# BrickPi_0_5.net
KiCad netlist of a schematic drawn in EAGLE
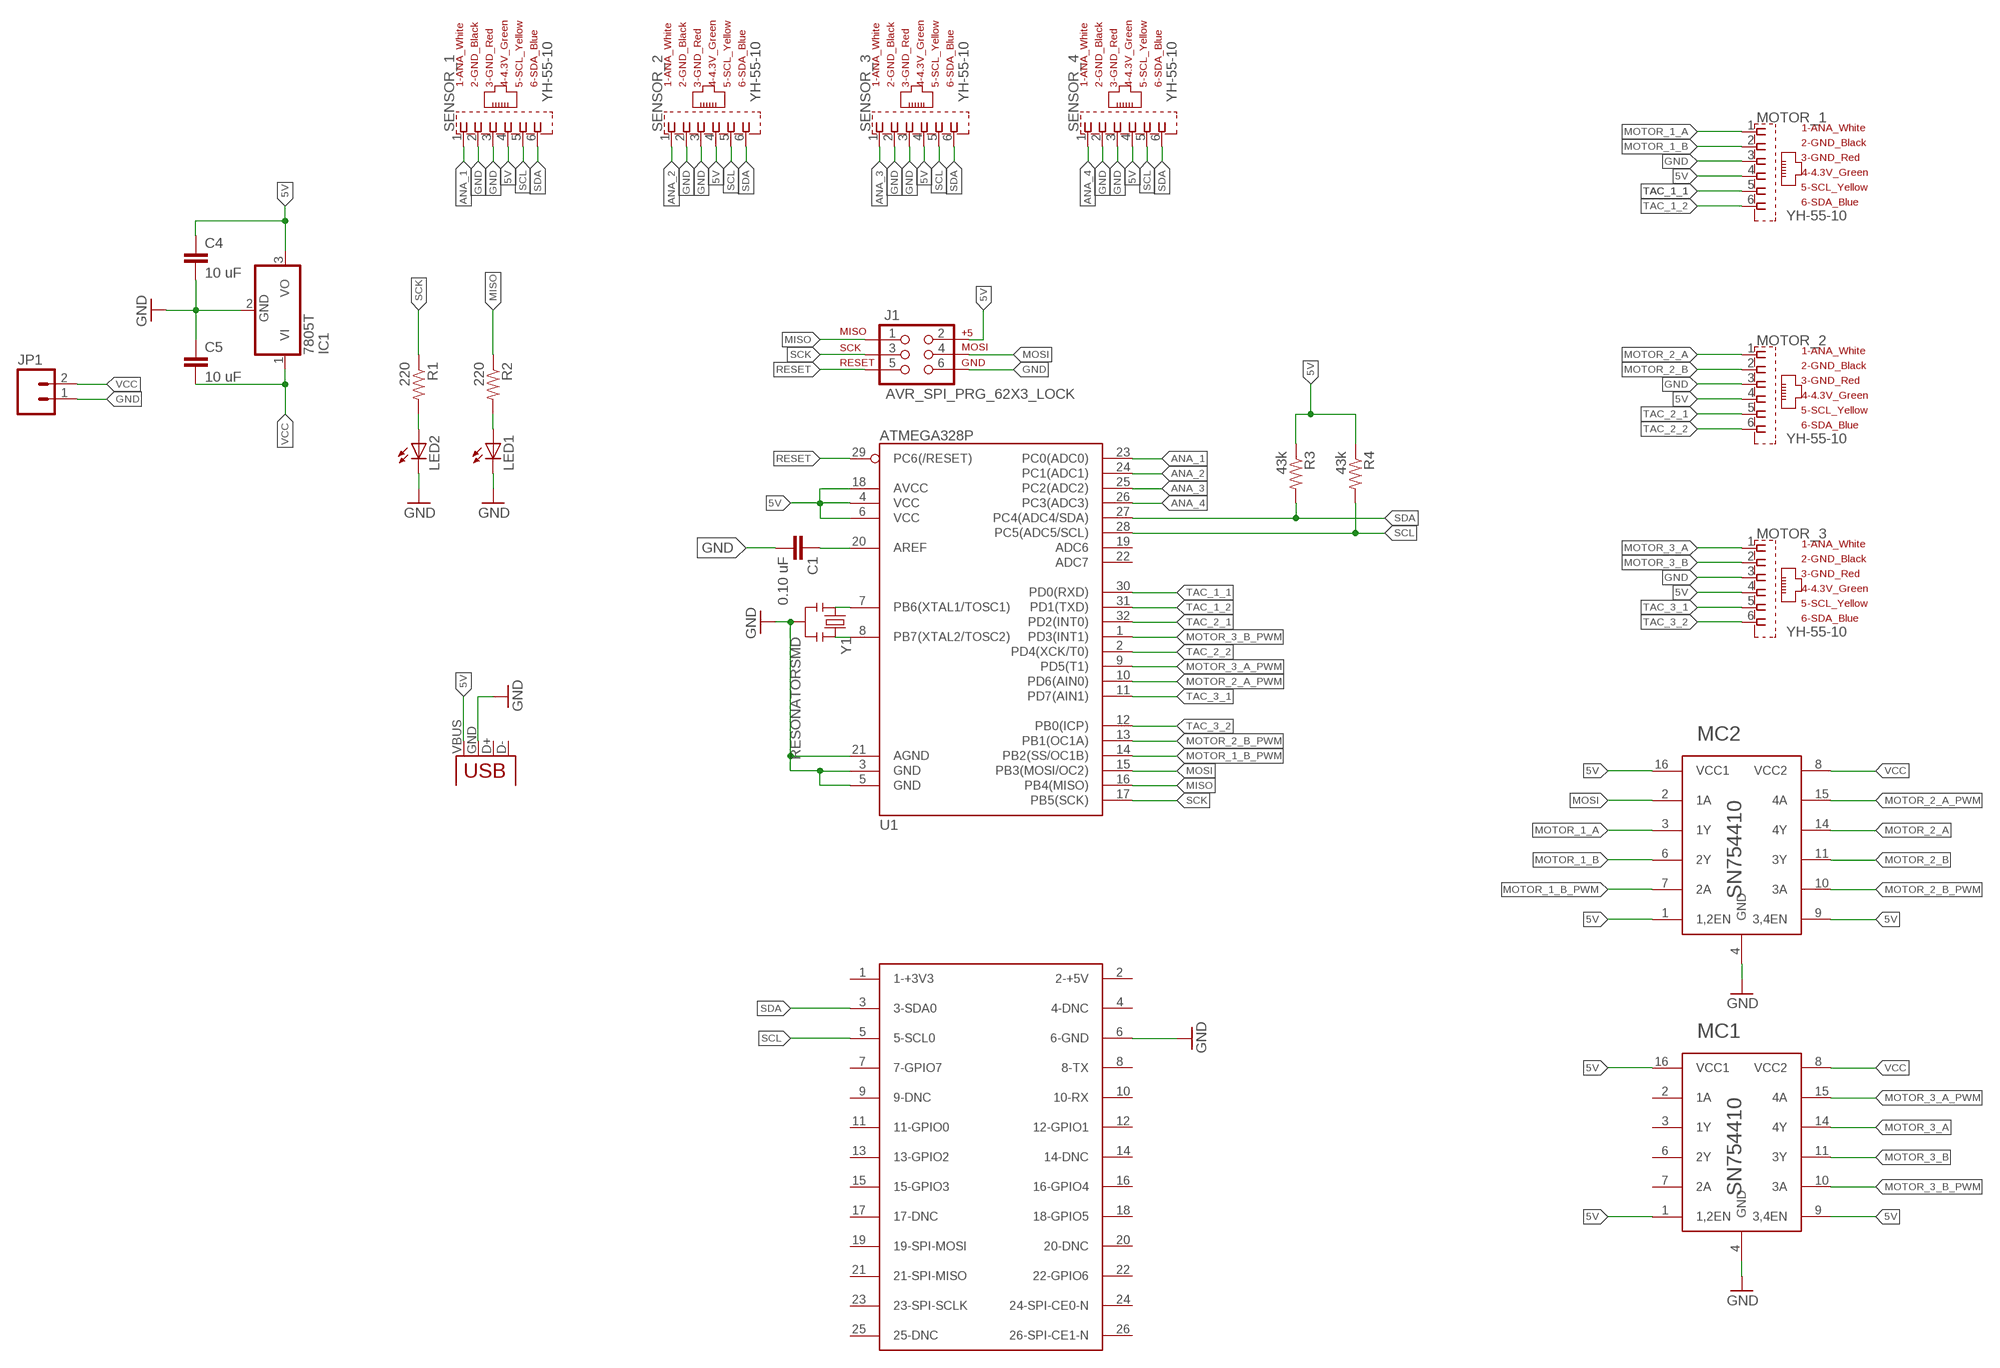
[diagram p0: schematic, sheet 1]

(export (version "E")
  (design (tool "Eeschema 10.0.6"))
  (components
    (comp (ref "C1")
      (value "0.10 uF")
      (footprint "eagle-import:0805")
      (libsource (lib "eagle-import") (part "CAP0805"))
    )
    (comp (ref "C4")
      (value "10 uF")
      (footprint "eagle-import:0805")
      (libsource (lib "eagle-import") (part "CAP0805"))
    )
    (comp (ref "C5")
      (value "10 uF")
      (footprint "eagle-import:0805")
      (libsource (lib "eagle-import") (part "CAP0805"))
    )
    (comp (ref "IC1")
      (value "7805T")
      (footprint "eagle-import:TO220H")
      (libsource (lib "eagle-import") (part "78T05"))
    )
    (comp (ref "J1")
      (value "AVR_SPI_PRG_62X3_LOCK")
      (footprint "eagle-import:2X3_LOCK")
      (libsource (lib "eagle-import") (part "AVR_SPI_PRG_62X3_LOCK"))
    )
    (comp (ref "JP1")
      (value "M02LOCK")
      (footprint "eagle-import:1X02_LOCK")
      (libsource (lib "eagle-import") (part "M02LOCK"))
    )
    (comp (ref "JP2")
      (value "USB-A-H")
      (footprint "eagle-import:USB-A-H")
      (libsource (lib "eagle-import") (part "USB-A-H"))
    )
    (comp (ref "LED1")
      (value "LED1206")
      (footprint "eagle-import:LED-1206")
      (libsource (lib "eagle-import") (part "LED1206"))
    )
    (comp (ref "LED2")
      (value "LED1206")
      (footprint "eagle-import:LED-1206")
      (libsource (lib "eagle-import") (part "LED1206"))
    )
    (comp (ref "MC1")
      (value "SN754410")
      (footprint "eagle-import:DIL16")
      (libsource (lib "eagle-import") (part "SN754410"))
    )
    (comp (ref "MC2")
      (value "SN754410")
      (footprint "eagle-import:DIL16")
      (libsource (lib "eagle-import") (part "SN754410"))
    )
    (comp (ref "MOTOR_1")
      (value "YH-55-10")
      (footprint "eagle-import:YH-55-10")
      (libsource (lib "eagle-import") (part "YH-55-10"))
    )
    (comp (ref "MOTOR_2")
      (value "YH-55-10")
      (footprint "eagle-import:YH-55-10")
      (libsource (lib "eagle-import") (part "YH-55-10"))
    )
    (comp (ref "MOTOR_3")
      (value "YH-55-10")
      (footprint "eagle-import:YH-55-10")
      (libsource (lib "eagle-import") (part "YH-55-10"))
    )
    (comp (ref "PI_OUTLINE")
      (value "RASPBERRY-PI")
      (footprint "eagle-import:RASPBERRY-PI")
      (libsource (lib "eagle-import") (part "RASPBERRY-PI"))
    )
    (comp (ref "R1")
      (value "220")
      (footprint "eagle-import:0603-RES")
      (libsource (lib "eagle-import") (part "220-5%"))
    )
    (comp (ref "R2")
      (value "220")
      (footprint "eagle-import:0603-RES")
      (libsource (lib "eagle-import") (part "220-5%"))
    )
    (comp (ref "R3")
      (value "43k")
      (footprint "eagle-import:0603-RES")
      (fields (field (name "PROD_ID") "RES-07866"))
      (libsource (lib "eagle-import") (part "220-5%"))
    )
    (comp (ref "R4")
      (value "43k")
      (footprint "eagle-import:0603-RES")
      (fields (field (name "PROD_ID") "RES-07866"))
      (libsource (lib "eagle-import") (part "220-5%"))
    )
    (comp (ref "SENSOR_1")
      (value "YH-55-10")
      (footprint "eagle-import:YH-55-10")
      (libsource (lib "eagle-import") (part "YH-55-10"))
    )
    (comp (ref "SENSOR_2")
      (value "YH-55-10")
      (footprint "eagle-import:YH-55-10")
      (libsource (lib "eagle-import") (part "YH-55-10"))
    )
    (comp (ref "SENSOR_3")
      (value "YH-55-10")
      (footprint "eagle-import:YH-55-10")
      (libsource (lib "eagle-import") (part "YH-55-10"))
    )
    (comp (ref "SENSOR_4")
      (value "YH-55-10")
      (footprint "eagle-import:YH-55-10")
      (libsource (lib "eagle-import") (part "YH-55-10"))
    )
    (comp (ref "U1")
      (value "ATMEGA328P")
      (footprint "eagle-import:TQFP32-08")
      (libsource (lib "eagle-import") (part "ATMEGA328_SMT"))
    )
    (comp (ref "Y1")
      (value "RESONATORSMD")
      (footprint "eagle-import:RESONATOR-SMD")
      (libsource (lib "eagle-import") (part "RESONATORSMD"))
    )
  )
  (nets
    (net (code "1") (name "5V") (class "Default")
      (node (ref "C4") (pin "1") (pinfunction "1_1") (pintype "passive"))
      (node (ref "IC1") (pin "3") (pinfunction "VO_3") (pintype "passive"))
      (node (ref "J1") (pin "2") (pinfunction "2_2") (pintype "passive"))
      (node (ref "JP2") (pin "VBUS") (pinfunction "GND_VBUS") (pintype "bidirectional"))
      (node (ref "MC1") (pin "1") (pinfunction "1,2EN_1") (pintype "bidirectional"))
      (node (ref "MC1") (pin "16") (pinfunction "VCC1_16") (pintype "power_in"))
      (node (ref "MC1") (pin "9") (pinfunction "3,4EN_9") (pintype "bidirectional"))
      (node (ref "MC2") (pin "1") (pinfunction "1,2EN_1") (pintype "bidirectional"))
      (node (ref "MC2") (pin "16") (pinfunction "VCC1_16") (pintype "power_in"))
      (node (ref "MC2") (pin "9") (pinfunction "3,4EN_9") (pintype "bidirectional"))
      (node (ref "MOTOR_1") (pin "4") (pinfunction "4_4.3V_GREEN_4") (pintype "passive"))
      (node (ref "MOTOR_2") (pin "4") (pinfunction "4_4.3V_GREEN_4") (pintype "passive"))
      (node (ref "MOTOR_3") (pin "4") (pinfunction "4_4.3V_GREEN_4") (pintype "passive"))
      (node (ref "R3") (pin "1") (pinfunction "1_1") (pintype "passive"))
      (node (ref "R4") (pin "1") (pinfunction "1_1") (pintype "passive"))
      (node (ref "SENSOR_1") (pin "4") (pinfunction "4_4.3V_GREEN_4") (pintype "passive"))
      (node (ref "SENSOR_2") (pin "4") (pinfunction "4_4.3V_GREEN_4") (pintype "passive"))
      (node (ref "SENSOR_3") (pin "4") (pinfunction "4_4.3V_GREEN_4") (pintype "passive"))
      (node (ref "SENSOR_4") (pin "4") (pinfunction "4_4.3V_GREEN_4") (pintype "passive"))
      (node (ref "U1") (pin "18") (pinfunction "AVCC_18") (pintype "bidirectional"))
      (node (ref "U1") (pin "4") (pinfunction "VCC_4") (pintype "bidirectional"))
      (node (ref "U1") (pin "6") (pinfunction "VCC_6") (pintype "bidirectional"))
    )
    (net (code "2") (name "ANA_1") (class "Default")
      (node (ref "SENSOR_1") (pin "1") (pinfunction "1_ANA_WHITE_1") (pintype "passive"))
      (node (ref "U1") (pin "23") (pinfunction "PC0(ADC0)_23") (pintype "bidirectional"))
    )
    (net (code "3") (name "ANA_2") (class "Default")
      (node (ref "SENSOR_2") (pin "1") (pinfunction "1_ANA_WHITE_1") (pintype "passive"))
      (node (ref "U1") (pin "24") (pinfunction "PC1(ADC1)_24") (pintype "bidirectional"))
    )
    (net (code "4") (name "ANA_3") (class "Default")
      (node (ref "SENSOR_3") (pin "1") (pinfunction "1_ANA_WHITE_1") (pintype "passive"))
      (node (ref "U1") (pin "25") (pinfunction "PC2(ADC2)_25") (pintype "bidirectional"))
    )
    (net (code "5") (name "ANA_4") (class "Default")
      (node (ref "SENSOR_4") (pin "1") (pinfunction "1_ANA_WHITE_1") (pintype "passive"))
      (node (ref "U1") (pin "26") (pinfunction "PC3(ADC3)_26") (pintype "bidirectional"))
    )
    (net (code "6") (name "GND") (class "Default")
      (node (ref "C1") (pin "2") (pinfunction "2_2") (pintype "passive"))
      (node (ref "C4") (pin "2") (pinfunction "2_2") (pintype "passive"))
      (node (ref "C5") (pin "1") (pinfunction "1_1") (pintype "passive"))
      (node (ref "IC1") (pin "2") (pinfunction "GND_2") (pintype "passive"))
      (node (ref "J1") (pin "6") (pinfunction "6_6") (pintype "passive"))
      (node (ref "JP1") (pin "1") (pinfunction "1_1") (pintype "passive"))
      (node (ref "JP2") (pin "GND") (pinfunction "VBUS_GND") (pintype "bidirectional"))
      (node (ref "LED1") (pin "C") (pinfunction "C_C") (pintype "passive"))
      (node (ref "LED2") (pin "C") (pinfunction "C_C") (pintype "passive"))
      (node (ref "MC1") (pin "4") (pinfunction "GND_4") (pintype "power_in"))
      (node (ref "MC2") (pin "4") (pinfunction "GND_4") (pintype "power_in"))
      (node (ref "MOTOR_1") (pin "3") (pinfunction "3_GND_RED_3") (pintype "passive"))
      (node (ref "MOTOR_2") (pin "3") (pinfunction "3_GND_RED_3") (pintype "passive"))
      (node (ref "MOTOR_3") (pin "3") (pinfunction "3_GND_RED_3") (pintype "passive"))
      (node (ref "PI_OUTLINE") (pin "6") (pinfunction "6-GND_6") (pintype "bidirectional"))
      (node (ref "SENSOR_1") (pin "2") (pinfunction "2_GND_BLACK_2") (pintype "passive"))
      (node (ref "SENSOR_1") (pin "3") (pinfunction "3_GND_RED_3") (pintype "passive"))
      (node (ref "SENSOR_2") (pin "2") (pinfunction "2_GND_BLACK_2") (pintype "passive"))
      (node (ref "SENSOR_2") (pin "3") (pinfunction "3_GND_RED_3") (pintype "passive"))
      (node (ref "SENSOR_3") (pin "2") (pinfunction "2_GND_BLACK_2") (pintype "passive"))
      (node (ref "SENSOR_3") (pin "3") (pinfunction "3_GND_RED_3") (pintype "passive"))
      (node (ref "SENSOR_4") (pin "2") (pinfunction "2_GND_BLACK_2") (pintype "passive"))
      (node (ref "SENSOR_4") (pin "3") (pinfunction "3_GND_RED_3") (pintype "passive"))
      (node (ref "U1") (pin "21") (pinfunction "AGND_21") (pintype "bidirectional"))
      (node (ref "U1") (pin "3") (pinfunction "GND_3") (pintype "bidirectional"))
      (node (ref "U1") (pin "5") (pinfunction "GND_5") (pintype "bidirectional"))
      (node (ref "Y1") (pin "2") (pinfunction "2_2") (pintype "passive"))
    )
    (net (code "7") (name "MISO") (class "Default")
      (node (ref "J1") (pin "1") (pinfunction "1_1") (pintype "passive"))
      (node (ref "R2") (pin "1") (pinfunction "1_1") (pintype "passive"))
      (node (ref "U1") (pin "16") (pinfunction "PB4(MISO)_16") (pintype "bidirectional"))
    )
    (net (code "8") (name "MOSI") (class "Default")
      (node (ref "J1") (pin "4") (pinfunction "4_4") (pintype "passive"))
      (node (ref "MC2") (pin "2") (pinfunction "1A_2") (pintype "bidirectional"))
      (node (ref "U1") (pin "15") (pinfunction "PB3(MOSI/OC2)_15") (pintype "bidirectional"))
    )
    (net (code "9") (name "MOTOR_1_A") (class "Default")
      (node (ref "MC2") (pin "3") (pinfunction "1Y_3") (pintype "bidirectional"))
      (node (ref "MOTOR_1") (pin "1") (pinfunction "1_ANA_WHITE_1") (pintype "passive"))
    )
    (net (code "10") (name "MOTOR_1_B") (class "Default")
      (node (ref "MC2") (pin "6") (pinfunction "2Y_6") (pintype "bidirectional"))
      (node (ref "MOTOR_1") (pin "2") (pinfunction "2_GND_BLACK_2") (pintype "passive"))
    )
    (net (code "11") (name "MOTOR_1_B_PWM") (class "Default")
      (node (ref "MC2") (pin "7") (pinfunction "2A_7") (pintype "bidirectional"))
      (node (ref "U1") (pin "14") (pinfunction "PB2(SS/OC1B)_14") (pintype "bidirectional"))
    )
    (net (code "12") (name "MOTOR_2_A") (class "Default")
      (node (ref "MC2") (pin "14") (pinfunction "4Y_14") (pintype "bidirectional"))
      (node (ref "MOTOR_2") (pin "1") (pinfunction "1_ANA_WHITE_1") (pintype "passive"))
    )
    (net (code "13") (name "MOTOR_2_A_PWM") (class "Default")
      (node (ref "MC2") (pin "15") (pinfunction "4A_15") (pintype "bidirectional"))
      (node (ref "U1") (pin "10") (pinfunction "PD6(AIN0)_10") (pintype "bidirectional"))
    )
    (net (code "14") (name "MOTOR_2_B") (class "Default")
      (node (ref "MC2") (pin "11") (pinfunction "3Y_11") (pintype "bidirectional"))
      (node (ref "MOTOR_2") (pin "2") (pinfunction "2_GND_BLACK_2") (pintype "passive"))
    )
    (net (code "15") (name "MOTOR_2_B_PWM") (class "Default")
      (node (ref "MC2") (pin "10") (pinfunction "3A_10") (pintype "bidirectional"))
      (node (ref "U1") (pin "13") (pinfunction "PB1(OC1A)_13") (pintype "bidirectional"))
    )
    (net (code "16") (name "MOTOR_3_A") (class "Default")
      (node (ref "MC1") (pin "14") (pinfunction "4Y_14") (pintype "bidirectional"))
      (node (ref "MOTOR_3") (pin "1") (pinfunction "1_ANA_WHITE_1") (pintype "passive"))
    )
    (net (code "17") (name "MOTOR_3_A_PWM") (class "Default")
      (node (ref "MC1") (pin "15") (pinfunction "4A_15") (pintype "bidirectional"))
      (node (ref "U1") (pin "9") (pinfunction "PD5(T1)_9") (pintype "bidirectional"))
    )
    (net (code "18") (name "MOTOR_3_B") (class "Default")
      (node (ref "MC1") (pin "11") (pinfunction "3Y_11") (pintype "bidirectional"))
      (node (ref "MOTOR_3") (pin "2") (pinfunction "2_GND_BLACK_2") (pintype "passive"))
    )
    (net (code "19") (name "MOTOR_3_B_PWM") (class "Default")
      (node (ref "MC1") (pin "10") (pinfunction "3A_10") (pintype "bidirectional"))
      (node (ref "U1") (pin "1") (pinfunction "PD3(INT1)_1") (pintype "bidirectional"))
    )
    (net (code "20") (name "Net-(LED1-PadA)") (class "Default")
      (node (ref "LED1") (pin "A") (pinfunction "A_A") (pintype "passive"))
      (node (ref "R2") (pin "2") (pinfunction "2_2") (pintype "passive"))
    )
    (net (code "21") (name "Net-(LED2-PadA)") (class "Default")
      (node (ref "LED2") (pin "A") (pinfunction "A_A") (pintype "passive"))
      (node (ref "R1") (pin "2") (pinfunction "2_2") (pintype "passive"))
    )
    (net (code "22") (name "Net-(U1-AREF)") (class "Default")
      (node (ref "C1") (pin "1") (pinfunction "1_1") (pintype "passive"))
      (node (ref "U1") (pin "20") (pinfunction "AREF_20") (pintype "bidirectional"))
    )
    (net (code "23") (name "Net-(U1-PB6(XTAL1{slash}TOSC1))") (class "Default")
      (node (ref "U1") (pin "7") (pinfunction "PB6(XTAL1/TOSC1)_7") (pintype "bidirectional"))
      (node (ref "Y1") (pin "1") (pinfunction "1_1") (pintype "passive"))
    )
    (net (code "24") (name "Net-(U1-PB7(XTAL2{slash}TOSC2))") (class "Default")
      (node (ref "U1") (pin "8") (pinfunction "PB7(XTAL2/TOSC2)_8") (pintype "bidirectional"))
      (node (ref "Y1") (pin "3") (pinfunction "3_3") (pintype "passive"))
    )
    (net (code "25") (name "RESET") (class "Default")
      (node (ref "J1") (pin "5") (pinfunction "5_5") (pintype "passive"))
      (node (ref "U1") (pin "29") (pinfunction "PC6(/RESET)_29") (pintype "bidirectional"))
    )
    (net (code "26") (name "SCK") (class "Default")
      (node (ref "J1") (pin "3") (pinfunction "3_3") (pintype "passive"))
      (node (ref "R1") (pin "1") (pinfunction "1_1") (pintype "passive"))
      (node (ref "U1") (pin "17") (pinfunction "PB5(SCK)_17") (pintype "bidirectional"))
    )
    (net (code "27") (name "SCL") (class "Default")
      (node (ref "PI_OUTLINE") (pin "5") (pinfunction "5-SCL0_5") (pintype "bidirectional"))
      (node (ref "R4") (pin "2") (pinfunction "2_2") (pintype "passive"))
      (node (ref "SENSOR_1") (pin "5") (pinfunction "5_SCL_YELLOW_5") (pintype "passive"))
      (node (ref "SENSOR_2") (pin "5") (pinfunction "5_SCL_YELLOW_5") (pintype "passive"))
      (node (ref "SENSOR_3") (pin "5") (pinfunction "5_SCL_YELLOW_5") (pintype "passive"))
      (node (ref "SENSOR_4") (pin "5") (pinfunction "5_SCL_YELLOW_5") (pintype "passive"))
      (node (ref "U1") (pin "28") (pinfunction "PC5(ADC5/SCL)_28") (pintype "bidirectional"))
    )
    (net (code "28") (name "SDA") (class "Default")
      (node (ref "PI_OUTLINE") (pin "3") (pinfunction "3-SDA0_3") (pintype "bidirectional"))
      (node (ref "R3") (pin "2") (pinfunction "2_2") (pintype "passive"))
      (node (ref "SENSOR_1") (pin "6") (pinfunction "6_SDA_BLUE_6") (pintype "passive"))
      (node (ref "SENSOR_2") (pin "6") (pinfunction "6_SDA_BLUE_6") (pintype "passive"))
      (node (ref "SENSOR_3") (pin "6") (pinfunction "6_SDA_BLUE_6") (pintype "passive"))
      (node (ref "SENSOR_4") (pin "6") (pinfunction "6_SDA_BLUE_6") (pintype "passive"))
      (node (ref "U1") (pin "27") (pinfunction "PC4(ADC4/SDA)_27") (pintype "bidirectional"))
    )
    (net (code "29") (name "TAC_1_1") (class "Default")
      (node (ref "MOTOR_1") (pin "5") (pinfunction "5_SCL_YELLOW_5") (pintype "passive"))
      (node (ref "U1") (pin "30") (pinfunction "PD0(RXD)_30") (pintype "bidirectional"))
    )
    (net (code "30") (name "TAC_1_2") (class "Default")
      (node (ref "MOTOR_1") (pin "6") (pinfunction "6_SDA_BLUE_6") (pintype "passive"))
      (node (ref "U1") (pin "31") (pinfunction "PD1(TXD)_31") (pintype "bidirectional"))
    )
    (net (code "31") (name "TAC_2_1") (class "Default")
      (node (ref "MOTOR_2") (pin "5") (pinfunction "5_SCL_YELLOW_5") (pintype "passive"))
      (node (ref "U1") (pin "32") (pinfunction "PD2(INT0)_32") (pintype "bidirectional"))
    )
    (net (code "32") (name "TAC_2_2") (class "Default")
      (node (ref "MOTOR_2") (pin "6") (pinfunction "6_SDA_BLUE_6") (pintype "passive"))
      (node (ref "U1") (pin "2") (pinfunction "PD4(XCK/T0)_2") (pintype "bidirectional"))
    )
    (net (code "33") (name "TAC_3_1") (class "Default")
      (node (ref "MOTOR_3") (pin "5") (pinfunction "5_SCL_YELLOW_5") (pintype "passive"))
      (node (ref "U1") (pin "11") (pinfunction "PD7(AIN1)_11") (pintype "bidirectional"))
    )
    (net (code "34") (name "TAC_3_2") (class "Default")
      (node (ref "MOTOR_3") (pin "6") (pinfunction "6_SDA_BLUE_6") (pintype "passive"))
      (node (ref "U1") (pin "12") (pinfunction "PB0(ICP)_12") (pintype "bidirectional"))
    )
    (net (code "35") (name "VCC") (class "Default")
      (node (ref "C5") (pin "2") (pinfunction "2_2") (pintype "passive"))
      (node (ref "IC1") (pin "1") (pinfunction "VI_1") (pintype "input"))
      (node (ref "JP1") (pin "2") (pinfunction "2_2") (pintype "passive"))
      (node (ref "MC1") (pin "8") (pinfunction "VCC2_8") (pintype "power_in"))
      (node (ref "MC2") (pin "8") (pinfunction "VCC2_8") (pintype "power_in"))
    )
    (net (code "36") (name "unconnected-(JP2-D+-PadD-)") (class "Default")
      (node (ref "JP2") (pin "D-") (pinfunction "D+_D-") (pintype "bidirectional"))
    )
    (net (code "37") (name "unconnected-(JP2-D--PadD+)") (class "Default")
      (node (ref "JP2") (pin "D+") (pinfunction "D-_D+") (pintype "bidirectional"))
    )
    (net (code "38") (name "unconnected-(MC1A-1A-Pad2)") (class "Default")
      (node (ref "MC1") (pin "2") (pinfunction "1A_2") (pintype "bidirectional"))
    )
    (net (code "39") (name "unconnected-(MC1A-1Y-Pad3)") (class "Default")
      (node (ref "MC1") (pin "3") (pinfunction "1Y_3") (pintype "bidirectional"))
    )
    (net (code "40") (name "unconnected-(MC1A-2A-Pad7)") (class "Default")
      (node (ref "MC1") (pin "7") (pinfunction "2A_7") (pintype "bidirectional"))
    )
    (net (code "41") (name "unconnected-(MC1A-2Y-Pad6)") (class "Default")
      (node (ref "MC1") (pin "6") (pinfunction "2Y_6") (pintype "bidirectional"))
    )
    (net (code "42") (name "unconnected-(PI_OUTLINE-1-+3V3-Pad1)") (class "Default")
      (node (ref "PI_OUTLINE") (pin "1") (pinfunction "1-+3V3_1") (pintype "bidirectional"))
    )
    (net (code "43") (name "unconnected-(PI_OUTLINE-2-+5V-Pad2)") (class "Default")
      (node (ref "PI_OUTLINE") (pin "2") (pinfunction "2-+5V_2") (pintype "bidirectional"))
    )
    (net (code "44") (name "unconnected-(PI_OUTLINE-4-DNC-Pad4)") (class "Default")
      (node (ref "PI_OUTLINE") (pin "4") (pinfunction "4-DNC_4") (pintype "bidirectional"))
    )
    (net (code "45") (name "unconnected-(PI_OUTLINE-7-GPIO7-Pad7)") (class "Default")
      (node (ref "PI_OUTLINE") (pin "7") (pinfunction "7-GPIO7_7") (pintype "bidirectional"))
    )
    (net (code "46") (name "unconnected-(PI_OUTLINE-8-TX-Pad8)") (class "Default")
      (node (ref "PI_OUTLINE") (pin "8") (pinfunction "8-TX_8") (pintype "bidirectional"))
    )
    (net (code "47") (name "unconnected-(PI_OUTLINE-9-DNC-Pad9)") (class "Default")
      (node (ref "PI_OUTLINE") (pin "9") (pinfunction "9-DNC_9") (pintype "bidirectional"))
    )
    (net (code "48") (name "unconnected-(PI_OUTLINE-10-RX-Pad10)") (class "Default")
      (node (ref "PI_OUTLINE") (pin "10") (pinfunction "10-RX_10") (pintype "bidirectional"))
    )
    (net (code "49") (name "unconnected-(PI_OUTLINE-11-GPIO0-Pad11)") (class "Default")
      (node (ref "PI_OUTLINE") (pin "11") (pinfunction "11-GPIO0_11") (pintype "bidirectional"))
    )
    (net (code "50") (name "unconnected-(PI_OUTLINE-12-GPIO1-Pad12)") (class "Default")
      (node (ref "PI_OUTLINE") (pin "12") (pinfunction "12-GPIO1_12") (pintype "bidirectional"))
    )
    (net (code "51") (name "unconnected-(PI_OUTLINE-13-GPIO2-Pad13)") (class "Default")
      (node (ref "PI_OUTLINE") (pin "13") (pinfunction "13-GPIO2_13") (pintype "bidirectional"))
    )
    (net (code "52") (name "unconnected-(PI_OUTLINE-14-DNC-Pad14)") (class "Default")
      (node (ref "PI_OUTLINE") (pin "14") (pinfunction "14-DNC_14") (pintype "bidirectional"))
    )
    (net (code "53") (name "unconnected-(PI_OUTLINE-15-GPIO3-Pad15)") (class "Default")
      (node (ref "PI_OUTLINE") (pin "15") (pinfunction "15-GPIO3_15") (pintype "bidirectional"))
    )
    (net (code "54") (name "unconnected-(PI_OUTLINE-16-GPIO4-Pad16)") (class "Default")
      (node (ref "PI_OUTLINE") (pin "16") (pinfunction "16-GPIO4_16") (pintype "bidirectional"))
    )
    (net (code "55") (name "unconnected-(PI_OUTLINE-17-DNC-Pad17)") (class "Default")
      (node (ref "PI_OUTLINE") (pin "17") (pinfunction "17-DNC_17") (pintype "bidirectional"))
    )
    (net (code "56") (name "unconnected-(PI_OUTLINE-18-GPIO5-Pad18)") (class "Default")
      (node (ref "PI_OUTLINE") (pin "18") (pinfunction "18-GPIO5_18") (pintype "bidirectional"))
    )
    (net (code "57") (name "unconnected-(PI_OUTLINE-19-SPI-MOSI-Pad19)") (class "Default")
      (node (ref "PI_OUTLINE") (pin "19") (pinfunction "19-SPI-MOSI_19") (pintype "bidirectional"))
    )
    (net (code "58") (name "unconnected-(PI_OUTLINE-20-DNC-Pad20)") (class "Default")
      (node (ref "PI_OUTLINE") (pin "20") (pinfunction "20-DNC_20") (pintype "bidirectional"))
    )
    (net (code "59") (name "unconnected-(PI_OUTLINE-21-SPI-MISO-Pad21)") (class "Default")
      (node (ref "PI_OUTLINE") (pin "21") (pinfunction "21-SPI-MISO_21") (pintype "bidirectional"))
    )
    (net (code "60") (name "unconnected-(PI_OUTLINE-22-GPIO6-Pad22)") (class "Default")
      (node (ref "PI_OUTLINE") (pin "22") (pinfunction "22-GPIO6_22") (pintype "bidirectional"))
    )
    (net (code "61") (name "unconnected-(PI_OUTLINE-23-SPI-SCLK-Pad23)") (class "Default")
      (node (ref "PI_OUTLINE") (pin "23") (pinfunction "23-SPI-SCLK_23") (pintype "bidirectional"))
    )
    (net (code "62") (name "unconnected-(PI_OUTLINE-24-SPI-CE0-N-Pad24)") (class "Default")
      (node (ref "PI_OUTLINE") (pin "24") (pinfunction "24-SPI-CE0-N_24") (pintype "bidirectional"))
    )
    (net (code "63") (name "unconnected-(PI_OUTLINE-25-DNC-Pad25)") (class "Default")
      (node (ref "PI_OUTLINE") (pin "25") (pinfunction "25-DNC_25") (pintype "bidirectional"))
    )
    (net (code "64") (name "unconnected-(PI_OUTLINE-26-SPI-CE1-N-Pad26)") (class "Default")
      (node (ref "PI_OUTLINE") (pin "26") (pinfunction "26-SPI-CE1-N_26") (pintype "bidirectional"))
    )
    (net (code "65") (name "unconnected-(U1-ADC6-Pad19)") (class "Default")
      (node (ref "U1") (pin "19") (pinfunction "ADC6_19") (pintype "bidirectional"))
    )
    (net (code "66") (name "unconnected-(U1-ADC7-Pad22)") (class "Default")
      (node (ref "U1") (pin "22") (pinfunction "ADC7_22") (pintype "bidirectional"))
    )
  )
)
